# SensWear_MCU.net
KiCad netlist of a schematic drawn in Altium Designer
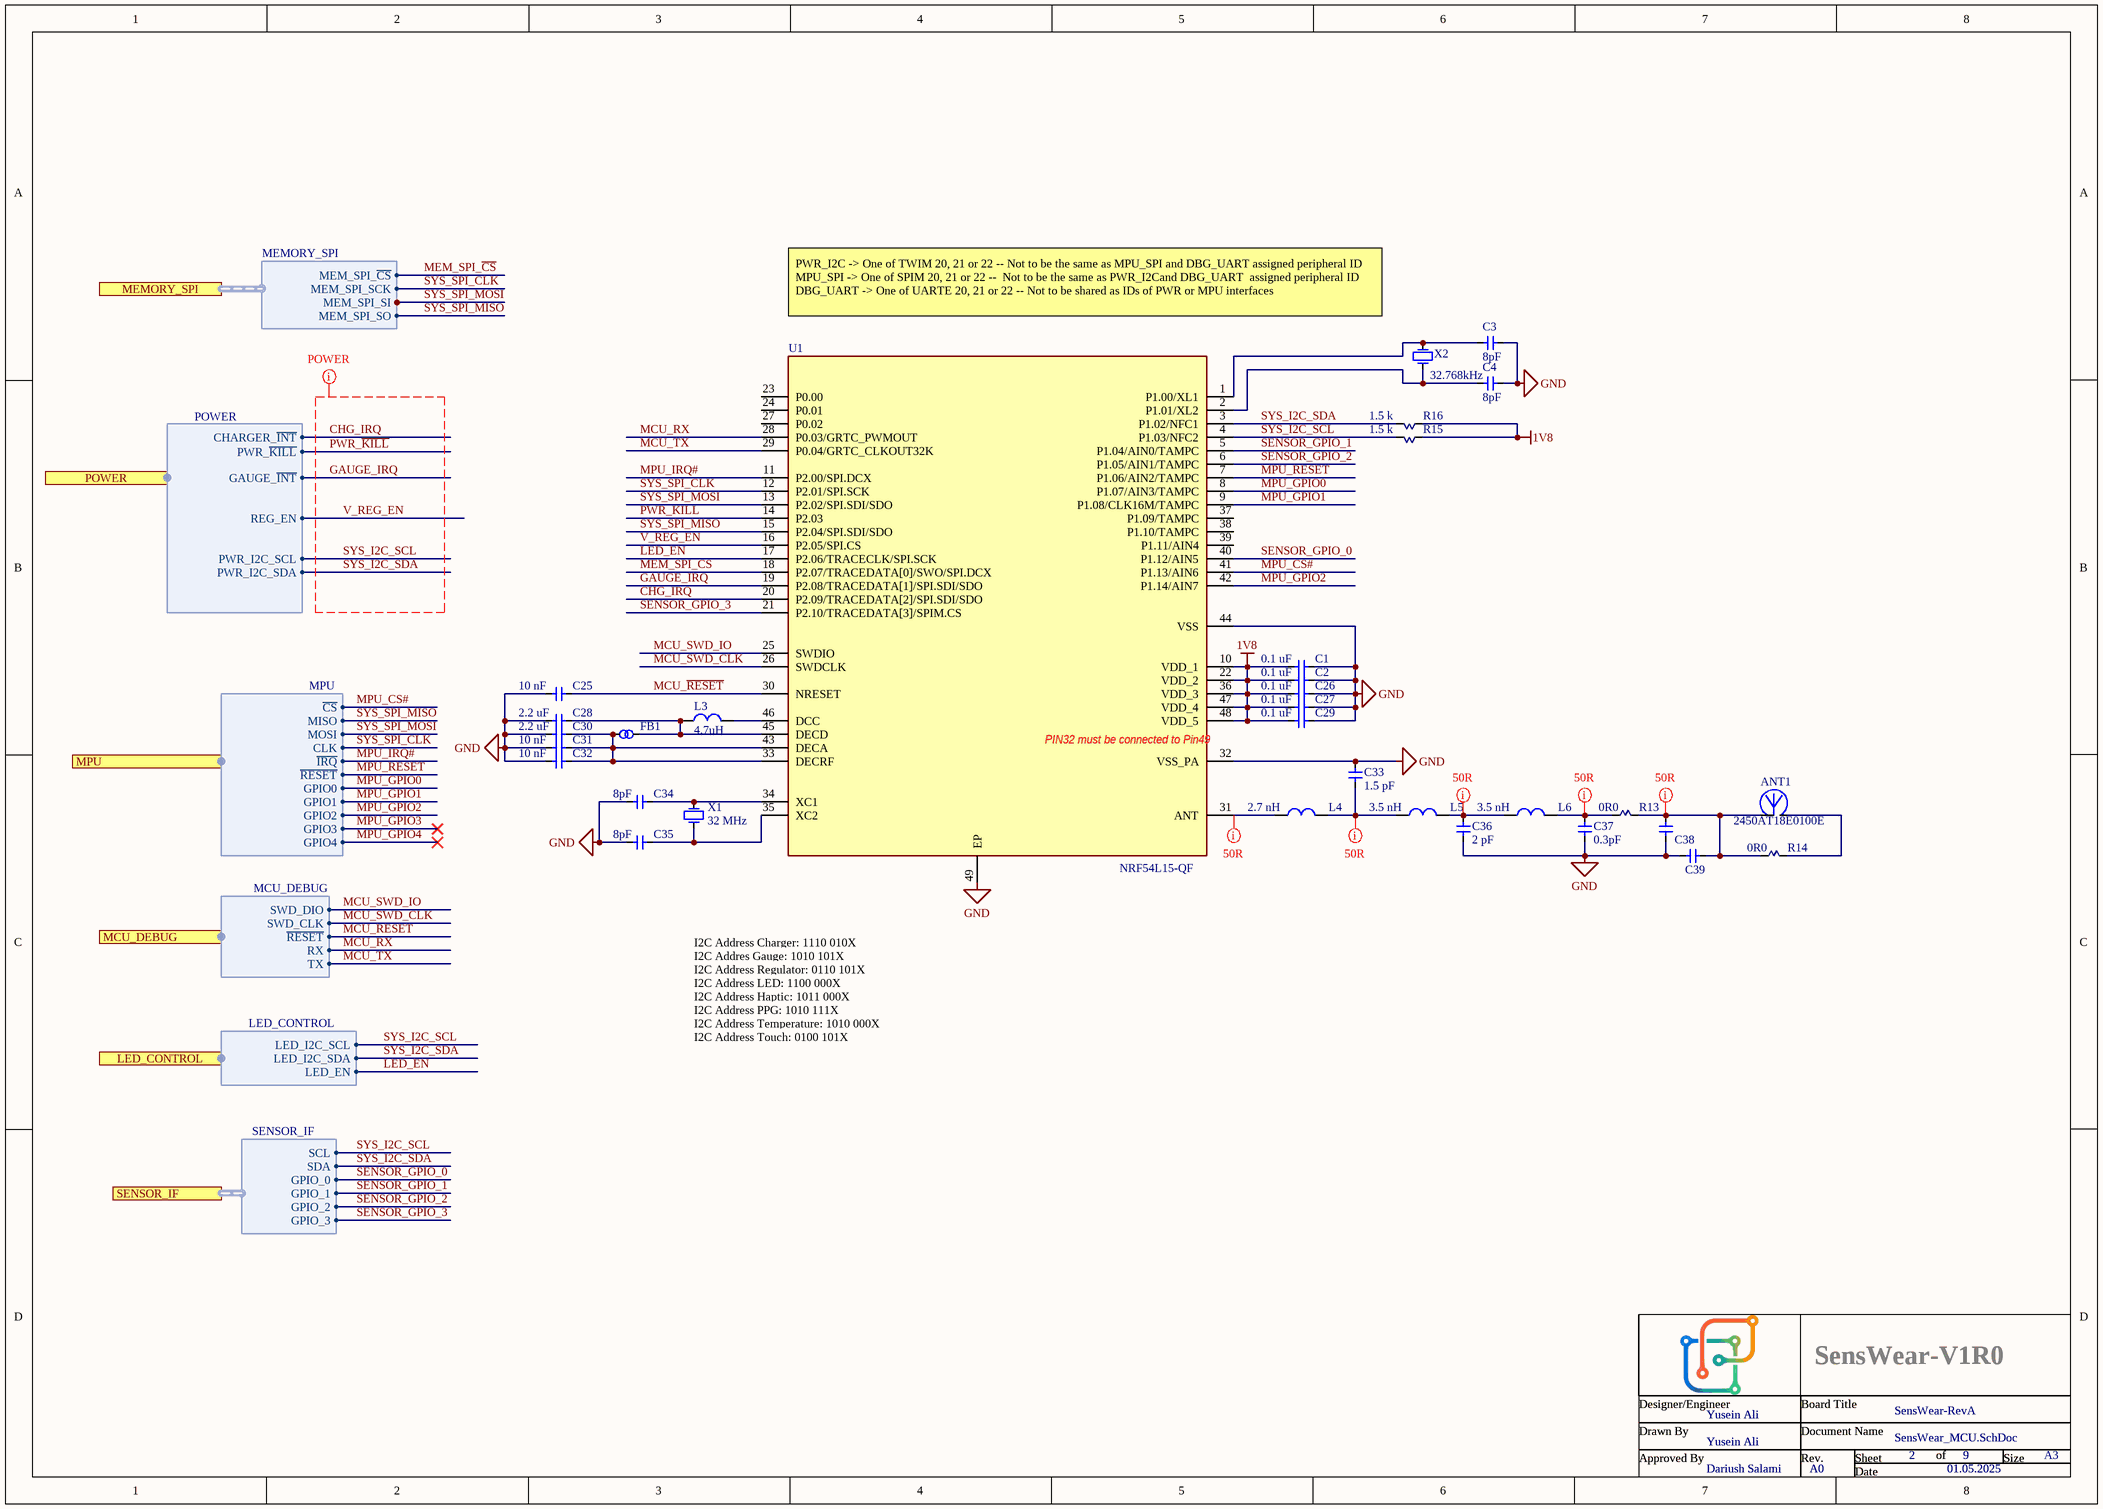
[diagram p0: SensWear_MCU.SchDoc]

(export (version "E")
  (design (tool "Eeschema 10.0.6"))
  (components
    (comp (ref "ANT1")
      (value "2450AT18E0100E")
      (footprint "ANTC3216X130N")
      (description "7 Inch Reel / Mini 2.45Ghz Chip Antenna")
      (fields (field (name "MANUFACTURER") "Johanson") (field (name "CHECKED") "TRUE"))
      (libsource (lib "RFComponents") (part "2450AT18E0100E"))
    )
    (comp (ref "C1")
      (value "0.1 uF")
      (footprint "CAPC1005X05N")
      (description "CAP CER 0.1UF 16V X5R 0402")
      (fields
        (field (name "MANUFACTURER") "Murata Electronics")
        (field (name "MANUFACTURER PART NUMBER") "GRM155R61C104KA88D")
      )
      (libsource (lib "OpenRingComponents") (part "GRM155R61C104KA88D"))
    )
    (comp (ref "C2")
      (value "0.1 uF")
      (footprint "CAPC1005X05N")
      (description "CAP CER 0.1UF 16V X5R 0402")
      (fields
        (field (name "MANUFACTURER") "Murata Electronics")
        (field (name "MANUFACTURER PART NUMBER") "GRM155R61C104KA88D")
      )
      (libsource (lib "OpenRingComponents") (part "GRM155R61C104KA88D"))
    )
    (comp (ref "C3")
      (value "8pF")
      (footprint "CAPC1005X05N")
      (description "Multilayer Ceramic Capacitors MLCC - SMD/SMT 0402 8.0pF 50volts C0G +/-0.05pF")
      (fields
        (field (name "MANUFACTURER") "Murata")
        (field (name "MANUFACTURER PART NUMBER") "GRM1555C1H8R0BA01D")
      )
      (libsource (lib "OpenRingComponents") (part "GRM1555C1H8R0BA01D"))
    )
    (comp (ref "C4")
      (value "8pF")
      (footprint "CAPC1005X05N")
      (description "Multilayer Ceramic Capacitors MLCC - SMD/SMT 0402 8.0pF 50volts C0G +/-0.05pF")
      (fields
        (field (name "MANUFACTURER") "Murata")
        (field (name "MANUFACTURER PART NUMBER") "GRM1555C1H8R0BA01D")
      )
      (libsource (lib "OpenRingComponents") (part "GRM1555C1H8R0BA01D"))
    )
    (comp (ref "C25")
      (value "10 nF")
      (footprint "CAPC1005X05N")
      (description "CAP CER 10000PF 50V X7R 0402")
      (fields
        (field (name "MANUFACTURER") "Murata Electronics North America")
        (field (name "MANUFACTURER PART NUMBER") "GRM155R71H103KA88D")
      )
      (libsource (lib "OpenRingComponents") (part "GRM155R71H103KA88D"))
    )
    (comp (ref "C26")
      (value "0.1 uF")
      (footprint "CAPC1005X05N")
      (description "CAP CER 0.1UF 16V X5R 0402")
      (fields
        (field (name "MANUFACTURER") "Murata Electronics")
        (field (name "MANUFACTURER PART NUMBER") "GRM155R61C104KA88D")
      )
      (libsource (lib "OpenRingComponents") (part "GRM155R61C104KA88D"))
    )
    (comp (ref "C27")
      (value "0.1 uF")
      (footprint "CAPC1005X05N")
      (description "CAP CER 0.1UF 16V X5R 0402")
      (fields
        (field (name "MANUFACTURER") "Murata Electronics")
        (field (name "MANUFACTURER PART NUMBER") "GRM155R61C104KA88D")
      )
      (libsource (lib "OpenRingComponents") (part "GRM155R61C104KA88D"))
    )
    (comp (ref "C28")
      (value "2.2 uF")
      (footprint "CAPC1005X05N")
      (description "CAP CER 2.2UF 10V X5R 0402")
      (fields
        (field (name "MANUFACTURER") "Murata Electronics North America")
        (field (name "MANUFACTURER PART NUMBER") "GRM155R61A225KE95D")
      )
      (libsource (lib "OpenRingComponents") (part "GRM155R61A225KE95D"))
    )
    (comp (ref "C29")
      (value "0.1 uF")
      (footprint "CAPC1005X05N")
      (description "CAP CER 0.1UF 16V X5R 0402")
      (fields
        (field (name "MANUFACTURER") "Murata Electronics")
        (field (name "MANUFACTURER PART NUMBER") "GRM155R61C104KA88D")
      )
      (libsource (lib "OpenRingComponents") (part "GRM155R61C104KA88D"))
    )
    (comp (ref "C30")
      (value "2.2 uF")
      (footprint "CAPC1005X05N")
      (description "CAP CER 2.2UF 10V X5R 0402")
      (fields
        (field (name "MANUFACTURER") "Murata Electronics North America")
        (field (name "MANUFACTURER PART NUMBER") "GRM155R61A225KE95D")
      )
      (libsource (lib "OpenRingComponents") (part "GRM155R61A225KE95D"))
    )
    (comp (ref "C31")
      (value "10 nF")
      (footprint "CAPC1005X05N")
      (description "CAP CER 10000PF 50V X7R 0402")
      (fields
        (field (name "MANUFACTURER") "Murata Electronics North America")
        (field (name "MANUFACTURER PART NUMBER") "GRM155R71H103KA88D")
      )
      (libsource (lib "OpenRingComponents") (part "GRM155R71H103KA88D"))
    )
    (comp (ref "C32")
      (value "10 nF")
      (footprint "CAPC1005X05N")
      (description "CAP CER 10000PF 50V X7R 0402")
      (fields
        (field (name "MANUFACTURER") "Murata Electronics North America")
        (field (name "MANUFACTURER PART NUMBER") "GRM155R71H103KA88D")
      )
      (libsource (lib "OpenRingComponents") (part "GRM155R71H103KA88D"))
    )
    (comp (ref "C33")
      (value "1.5 pF")
      (footprint "CAPC1005X05N")
      (description "Multilayer Ceramic Capacitor, 1.5 pF, 50 V, ï¿½ 0.1pF, C0G (NP0), 0402 [1005 Metric]")
      (fields
        (field (name "MANUFACTURER") "Murata")
        (field (name "MANUFACTURER PART NUMBER") "GJM1555C1H1R5BB01D")
      )
      (libsource (lib "OpenRingComponents") (part "GJM1555C1H1R5BB01D"))
    )
    (comp (ref "C34")
      (value "8pF")
      (footprint "CAPC1005X05N")
      (description "Multilayer Ceramic Capacitors MLCC - SMD/SMT 0402 8.0pF 50volts C0G +/-0.05pF")
      (fields
        (field (name "MANUFACTURER") "Murata")
        (field (name "MANUFACTURER PART NUMBER") "GRM1555C1H8R0BA01D")
      )
      (libsource (lib "OpenRingComponents") (part "GRM1555C1H8R0BA01D"))
    )
    (comp (ref "C35")
      (value "8pF")
      (footprint "CAPC1005X05N")
      (description "Multilayer Ceramic Capacitors MLCC - SMD/SMT 0402 8.0pF 50volts C0G +/-0.05pF")
      (fields
        (field (name "MANUFACTURER") "Murata")
        (field (name "MANUFACTURER PART NUMBER") "GRM1555C1H8R0BA01D")
      )
      (libsource (lib "OpenRingComponents") (part "GRM1555C1H8R0BA01D"))
    )
    (comp (ref "C36")
      (value "2 pF")
      (footprint "CAPC1005X05N")
      (description "0402 2 pF 50V ±0.05 pF Tolerance C0G SMT Multilayer Ceramic Capacitor")
      (fields
        (field (name "MANUFACTURER") "Murata")
        (field (name "MANUFACTURER PART NUMBER") "GJM1555C1H2R0WB01D")
      )
      (libsource (lib "Passives") (part "GJM1555C1H2R0WB01D"))
    )
    (comp (ref "C37")
      (value "0.3pF")
      (footprint "INDC1005X06N")
      (description "0402 0.3 pF 50V ±0.05 pF Tolerance C0G SMT Multilayer Ceramic Capacitor")
      (fields
        (field (name "MANUFACTURER") "Murata")
        (field (name "MANUFACTURER PART NUMBER") "GJM1555C1HR30WB01D")
      )
      (libsource (lib "OpenRingComponents") (part "GJM1555C1HR30WB01D"))
    )
    (comp (ref "C38")
      (value "NC")
      (footprint "CAPC1005X05N")
      (libsource (lib "OpenRingComponents") (part "CAPACITOR"))
    )
    (comp (ref "C39")
      (value "NC")
      (footprint "CAPC1005X05N")
      (libsource (lib "OpenRingComponents") (part "CAPACITOR"))
    )
    (comp (ref "FB1")
      (value "BLM15AG121SN1D")
      (footprint "INDC1005X06N")
      (description "Ferrite Beads Multi-Layer 120Ohm 25% 100MHz 550mA 190mOhm DCR 0402 Paper T/R")
      (fields (field (name "MANUFACTURER") "Murata") (field (name "TOLERANCE") "25%"))
      (libsource (lib "OpenRingComponents") (part "BLM15AG121SN1D"))
    )
    (comp (ref "L3")
      (value "4.7uH")
      (footprint "INDC1005X06N")
      (description "Inductor Power Chip Shielded Multi-Layer 4.7uH 20% 1MHz Ferrite 0.08A 0.78Ohm DCR 0603 T/R")
      (fields
        (field (name "MANUFACTURER") "Murata")
        (field (name "MANUFACTURER PART NUMBER") "LQM18FN4R7M00D")
      )
      (libsource (lib "Passives") (part "LQM18FN4R7M00D"))
    )
    (comp (ref "L4")
      (value "2.7 nH")
      (footprint "INDC1005X06N")
      (description "Inductor Chip 2.7nH 0.1nH Tolerance 2-Pin 0402 Paper T/R")
      (fields
        (field (name "MANUFACTURER") "Murata")
        (field (name "MANUFACTURER PART NUMBER") "LQG15WH2N7B02D")
      )
      (libsource (lib "OpenRingComponents") (part "LQG15WH2N7B02D"))
    )
    (comp (ref "L5")
      (value "3.5 nH")
      (footprint "INDC1005X06N")
      (description "Inductor Chip 3.5nH 0.1nH Tolerance 2-Pin 0402 Paper T/R")
      (fields
        (field (name "MANUFACTURER") "Murata")
        (field (name "MANUFACTURER PART NUMBER") "LQG15WH3N5B02D")
      )
      (libsource (lib "OpenRingComponents") (part "LQG15WH3N5B02D"))
    )
    (comp (ref "L6")
      (value "3.5 nH")
      (footprint "INDC1005X06N")
      (description "Inductor Chip 3.5nH 0.1nH Tolerance 2-Pin 0402 Paper T/R")
      (fields
        (field (name "MANUFACTURER") "Murata")
        (field (name "MANUFACTURER PART NUMBER") "LQG15WH3N5B02D")
      )
      (libsource (lib "OpenRingComponents") (part "LQG15WH3N5B02D"))
    )
    (comp (ref "R13")
      (value "0R0")
      (footprint "RESC1005X04N")
      (description "RES SMD 0.0OHM JUMPER 1/10W 0402")
      (fields
        (field (name "MANUFACTURER") "Panasonic Electronic Components")
        (field (name "MANUFACTURER PART NUMBER") "ERJ-2GE0R00X")
      )
      (libsource (lib "OpenRingComponents") (part "ERJ-2GE0R00X"))
    )
    (comp (ref "R14")
      (value "0R0")
      (footprint "RESC1005X04N")
      (description "RES SMD 0.0OHM JUMPER 1/10W 0402")
      (fields
        (field (name "MANUFACTURER") "Panasonic Electronic Components")
        (field (name "MANUFACTURER PART NUMBER") "ERJ-2GE0R00X")
      )
      (libsource (lib "OpenRingComponents") (part "ERJ-2GE0R00X"))
    )
    (comp (ref "R15")
      (value "1.5 k")
      (footprint "RESC1005X04N")
      (description "RES SMD 1.5K OHM 1% 1/10W 0402")
      (fields
        (field (name "MANUFACTURER") "Panasonic Electronic Components")
        (field (name "MANUFACTURER PART NUMBER") "ERJ-2RKF1501X")
      )
      (libsource (lib "OpenRingComponents") (part "ERJ-2RKF1501X"))
    )
    (comp (ref "R16")
      (value "1.5 k")
      (footprint "RESC1005X04N")
      (description "RES SMD 1.5K OHM 1% 1/10W 0402")
      (fields
        (field (name "MANUFACTURER") "Panasonic Electronic Components")
        (field (name "MANUFACTURER PART NUMBER") "ERJ-2RKF1501X")
      )
      (libsource (lib "OpenRingComponents") (part "ERJ-2RKF1501X"))
    )
    (comp (ref "U1")
      (value "NRF54L15-QF")
      (footprint "QFN40P600X600X95-49N")
      (description "nRF54L15 SoC with Arm Cortex-M33 processor")
      (fields
        (field (name "MANUFACTURER") "Nordic Semiconductor")
        (field (name "MANUFACTURER PART NUMBER") "NRF54L15-QFAA-R")
      )
      (libsource (lib "OpenRingComponents") (part "NRF54L15-QFAA-R"))
    )
    (comp (ref "X1")
      (value "32 MHz")
      (footprint "FP-ABM11W-MFG")
      (description "CRYSTAL 32.0000MHZ 8PF SMD, 2x1.6mm, RoHS")
      (fields
        (field (name "MANUFACTURER") "Abracon")
        (field (name "MANUFACTURER PART NUMBER") "ABM11W-32.0000MHZ-8-B1U-T3")
        (field (name "CHECKED") "TRUE")
      )
      (libsource (lib "Passives") (part "ABM11W-32.0000MHZ-8-B1U-T3"))
    )
    (comp (ref "X2")
      (value "32.768kHz")
      (footprint "Abracon_ABS6_2012X06L")
      (description "CRYSTAL 32.768 KHZ 12.5 PF SMD")
      (fields
        (field (name "MANUFACTURER") "Abracon Corporation")
        (field (name "MANUFACTURER PART NUMBER") "ABS06-32.768KHZ-1-T")
      )
      (libsource (lib "OpenRingComponents") (part "ABS06-32.768KHZ-1-T"))
    )
  )
  (nets
    (net (code "7") (name "/CHG_IRQ") (class "Default")
      (node (ref "U1") (pin "20") (pinfunction "P2.09/TRACEDATA[2]/SPI.SDI/SDO_20") (pintype "passive"))
    )
    (net (code "8") (name "/GAUGE_IRQ") (class "Default")
      (node (ref "U1") (pin "19") (pinfunction "P2.08/TRACEDATA[1]/SPI.SDI/SDO_19") (pintype "passive"))
    )
    (net (code "9") (name "/LED_EN") (class "Default")
      (node (ref "U1") (pin "17") (pinfunction "P2.06/TRACECLK/SPI.SCK_17") (pintype "passive"))
    )
    (net (code "10") (name "/MCU_RX") (class "Default")
      (node (ref "U1") (pin "28") (pinfunction "P0.03/GRTC_PWMOUT_28") (pintype "passive"))
    )
    (net (code "11") (name "/MCU_SWD_CLK") (class "Default")
      (node (ref "U1") (pin "26") (pinfunction "SWDCLK_26") (pintype "passive"))
    )
    (net (code "12") (name "/MCU_SWD_IO") (class "Default")
      (node (ref "U1") (pin "25") (pinfunction "SWDIO_25") (pintype "passive"))
    )
    (net (code "13") (name "/MCU_TX") (class "Default")
      (node (ref "U1") (pin "29") (pinfunction "P0.04/GRTC_CLKOUT32K_29") (pintype "passive"))
    )
    (net (code "14") (name "/MCU_~{RESET}") (class "Default")
      (node (ref "C25") (pin "2") (pinfunction "2_2") (pintype "passive"))
      (node (ref "U1") (pin "30") (pinfunction "NRESET_30") (pintype "passive"))
    )
    (net (code "15") (name "/MEM_SPI_~{CS}") (class "Default")
      (node (ref "U1") (pin "18") (pinfunction "P2.07/TRACEDATA[0]/SWO/SPI.DCX_18") (pintype "passive"))
    )
    (net (code "16") (name "/MPU_CS#") (class "Default")
      (node (ref "U1") (pin "41") (pinfunction "P1.13/AIN6_41") (pintype "passive"))
    )
    (net (code "17") (name "/MPU_GPIO0") (class "Default")
      (node (ref "U1") (pin "8") (pinfunction "P1.07/AIN3/TAMPC_8") (pintype "passive"))
    )
    (net (code "18") (name "/MPU_GPIO1") (class "Default")
      (node (ref "U1") (pin "9") (pinfunction "P1.08/CLK16M/TAMPC_9") (pintype "passive"))
    )
    (net (code "19") (name "/MPU_GPIO2") (class "Default")
      (node (ref "U1") (pin "42") (pinfunction "P1.14/AIN7_42") (pintype "passive"))
    )
    (net (code "22") (name "/MPU_IRQ#") (class "Default")
      (node (ref "U1") (pin "11") (pinfunction "P2.00/SPI.DCX_11") (pintype "passive"))
    )
    (net (code "23") (name "/MPU_~{RESET}") (class "Default")
      (node (ref "U1") (pin "7") (pinfunction "P1.06/AIN2/TAMPC_7") (pintype "passive"))
    )
    (net (code "24") (name "/PWR_~{KILL}") (class "Default")
      (node (ref "U1") (pin "14") (pinfunction "P2.03_14") (pintype "passive"))
    )
    (net (code "25") (name "/SENSOR_GPIO_0") (class "Default")
      (node (ref "U1") (pin "40") (pinfunction "P1.12/AIN5_40") (pintype "passive"))
    )
    (net (code "26") (name "/SENSOR_GPIO_1") (class "Default")
      (node (ref "U1") (pin "5") (pinfunction "P1.04/AIN0/TAMPC_5") (pintype "passive"))
    )
    (net (code "27") (name "/SENSOR_GPIO_2") (class "Default")
      (node (ref "U1") (pin "6") (pinfunction "P1.05/AIN1/TAMPC_6") (pintype "passive"))
    )
    (net (code "28") (name "/SENSOR_GPIO_3") (class "Default")
      (node (ref "U1") (pin "21") (pinfunction "P2.10/TRACEDATA[3]/SPIM.CS_21") (pintype "passive"))
    )
    (net (code "29") (name "/SYS_I2C_SCL") (class "Default")
      (node (ref "R15") (pin "2") (pinfunction "2_2") (pintype "passive"))
      (node (ref "U1") (pin "4") (pinfunction "P1.03/NFC2_4") (pintype "passive"))
    )
    (net (code "30") (name "/SYS_I2C_SDA") (class "Default")
      (node (ref "R16") (pin "2") (pinfunction "2_2") (pintype "passive"))
      (node (ref "U1") (pin "3") (pinfunction "P1.02/NFC1_3") (pintype "passive"))
    )
    (net (code "31") (name "/SYS_SPI_CLK") (class "Default")
      (node (ref "U1") (pin "12") (pinfunction "P2.01/SPI.SCK_12") (pintype "passive"))
    )
    (net (code "32") (name "/SYS_SPI_MISO") (class "Default")
      (node (ref "U1") (pin "15") (pinfunction "P2.04/SPI.SDI/SDO_15") (pintype "passive"))
    )
    (net (code "33") (name "/SYS_SPI_MOSI") (class "Default")
      (node (ref "U1") (pin "13") (pinfunction "P2.02/SPI.SDI/SDO_13") (pintype "passive"))
    )
    (net (code "34") (name "/V_REG_EN") (class "Default")
      (node (ref "U1") (pin "16") (pinfunction "P2.05/SPI.CS_16") (pintype "passive"))
    )
    (net (code "41") (name "1V8") (class "Default")
      (node (ref "C1") (pin "1") (pinfunction "1_1") (pintype "passive"))
      (node (ref "C2") (pin "1") (pinfunction "1_1") (pintype "passive"))
      (node (ref "C26") (pin "1") (pinfunction "1_1") (pintype "passive"))
      (node (ref "C27") (pin "1") (pinfunction "1_1") (pintype "passive"))
      (node (ref "C29") (pin "1") (pinfunction "1_1") (pintype "passive"))
      (node (ref "R15") (pin "1") (pinfunction "1_1") (pintype "passive"))
      (node (ref "R16") (pin "1") (pinfunction "1_1") (pintype "passive"))
      (node (ref "U1") (pin "10") (pinfunction "VDD_1_10") (pintype "passive"))
      (node (ref "U1") (pin "22") (pinfunction "VDD_2_22") (pintype "passive"))
      (node (ref "U1") (pin "36") (pinfunction "VDD_3_36") (pintype "passive"))
      (node (ref "U1") (pin "47") (pinfunction "VDD_4_47") (pintype "passive"))
      (node (ref "U1") (pin "48") (pinfunction "VDD_5_48") (pintype "passive"))
    )
    (net (code "42") (name "GND") (class "Default")
      (node (ref "C1") (pin "2") (pinfunction "2_2") (pintype "passive"))
      (node (ref "C2") (pin "2") (pinfunction "2_2") (pintype "passive"))
      (node (ref "C25") (pin "1") (pinfunction "1_1") (pintype "passive"))
      (node (ref "C26") (pin "2") (pinfunction "2_2") (pintype "passive"))
      (node (ref "C27") (pin "2") (pinfunction "2_2") (pintype "passive"))
      (node (ref "C28") (pin "1") (pinfunction "1_1") (pintype "passive"))
      (node (ref "C29") (pin "2") (pinfunction "2_2") (pintype "passive"))
      (node (ref "C3") (pin "2") (pinfunction "2_2") (pintype "passive"))
      (node (ref "C30") (pin "1") (pinfunction "1_1") (pintype "passive"))
      (node (ref "C31") (pin "1") (pinfunction "1_1") (pintype "passive"))
      (node (ref "C32") (pin "1") (pinfunction "1_1") (pintype "passive"))
      (node (ref "C33") (pin "2") (pinfunction "2_2") (pintype "passive"))
      (node (ref "C34") (pin "1") (pinfunction "1_1") (pintype "passive"))
      (node (ref "C35") (pin "1") (pinfunction "1_1") (pintype "passive"))
      (node (ref "C36") (pin "1") (pinfunction "1_1") (pintype "passive"))
      (node (ref "C37") (pin "1") (pinfunction "1_1") (pintype "passive"))
      (node (ref "C38") (pin "1") (pinfunction "1_1") (pintype "passive"))
      (node (ref "C39") (pin "2") (pinfunction "2_2") (pintype "passive"))
      (node (ref "C4") (pin "1") (pinfunction "1_1") (pintype "passive"))
      (node (ref "U1") (pin "32") (pinfunction "VSS_PA_32") (pintype "passive"))
      (node (ref "U1") (pin "44") (pinfunction "VSS_44") (pintype "passive"))
      (node (ref "U1") (pin "49") (pinfunction "EP_49") (pintype "passive"))
    )
    (net (code "43") (name "Net-(ANT1-Pad1)") (class "Default")
      (node (ref "ANT1") (pin "1") (pinfunction "1_1") (pintype "passive"))
      (node (ref "C38") (pin "2") (pinfunction "2_2") (pintype "passive"))
      (node (ref "C39") (pin "1") (pinfunction "1_1") (pintype "passive"))
      (node (ref "R13") (pin "2") (pinfunction "2_2") (pintype "passive"))
      (node (ref "R14") (pin "1") (pinfunction "1_1") (pintype "passive"))
    )
    (net (code "44") (name "Net-(ANT1-Pad2)") (class "Default")
      (node (ref "ANT1") (pin "2") (pinfunction "2_2") (pintype "passive"))
      (node (ref "R14") (pin "2") (pinfunction "2_2") (pintype "passive"))
    )
    (net (code "45") (name "Net-(C33-Pad1)") (class "Default")
      (node (ref "C33") (pin "1") (pinfunction "1_1") (pintype "passive"))
      (node (ref "L4") (pin "2") (pinfunction "2_2") (pintype "passive"))
      (node (ref "L5") (pin "1") (pinfunction "1_1") (pintype "passive"))
    )
    (net (code "46") (name "Net-(C36-Pad2)") (class "Default")
      (node (ref "C36") (pin "2") (pinfunction "2_2") (pintype "passive"))
      (node (ref "L5") (pin "2") (pinfunction "2_2") (pintype "passive"))
      (node (ref "L6") (pin "1") (pinfunction "1_1") (pintype "passive"))
    )
    (net (code "47") (name "Net-(C37-Pad2)") (class "Default")
      (node (ref "C37") (pin "2") (pinfunction "2_2") (pintype "passive"))
      (node (ref "L6") (pin "2") (pinfunction "2_2") (pintype "passive"))
      (node (ref "R13") (pin "1") (pinfunction "1_1") (pintype "passive"))
    )
    (net (code "48") (name "Net-(U1-ANT)") (class "Default")
      (node (ref "L4") (pin "1") (pinfunction "1_1") (pintype "passive"))
      (node (ref "U1") (pin "31") (pinfunction "ANT_31") (pintype "passive"))
    )
    (net (code "49") (name "Net-(U1-DCC)") (class "Default")
      (node (ref "L3") (pin "2") (pinfunction "2_2") (pintype "passive"))
      (node (ref "U1") (pin "46") (pinfunction "DCC_46") (pintype "passive"))
    )
    (net (code "50") (name "Net-(U1-DECA)") (class "Default")
      (node (ref "C30") (pin "2") (pinfunction "2_2") (pintype "passive"))
      (node (ref "C31") (pin "2") (pinfunction "2_2") (pintype "passive"))
      (node (ref "C32") (pin "2") (pinfunction "2_2") (pintype "passive"))
      (node (ref "FB1") (pin "1") (pinfunction "1_1") (pintype "passive"))
      (node (ref "U1") (pin "33") (pinfunction "DECRF_33") (pintype "passive"))
      (node (ref "U1") (pin "43") (pinfunction "DECA_43") (pintype "passive"))
    )
    (net (code "51") (name "Net-(U1-DECD)") (class "Default")
      (node (ref "C28") (pin "2") (pinfunction "2_2") (pintype "passive"))
      (node (ref "FB1") (pin "2") (pinfunction "2_2") (pintype "passive"))
      (node (ref "L3") (pin "1") (pinfunction "1_1") (pintype "passive"))
      (node (ref "U1") (pin "45") (pinfunction "DECD_45") (pintype "passive"))
    )
    (net (code "52") (name "Net-(U1-P1.00{slash}XL1)") (class "Default")
      (node (ref "C3") (pin "1") (pinfunction "1_1") (pintype "passive"))
      (node (ref "U1") (pin "1") (pinfunction "P1.00/XL1_1") (pintype "passive"))
      (node (ref "X2") (pin "2") (pinfunction "OSC2_2") (pintype "passive"))
    )
    (net (code "53") (name "Net-(U1-P1.01{slash}XL2)") (class "Default")
      (node (ref "C4") (pin "2") (pinfunction "2_2") (pintype "passive"))
      (node (ref "U1") (pin "2") (pinfunction "P1.01/XL2_2") (pintype "passive"))
      (node (ref "X2") (pin "1") (pinfunction "OSC1_1") (pintype "passive"))
    )
    (net (code "54") (name "Net-(U1-XC1)") (class "Default")
      (node (ref "C34") (pin "2") (pinfunction "2_2") (pintype "passive"))
      (node (ref "U1") (pin "34") (pinfunction "XC1_34") (pintype "passive"))
      (node (ref "X1") (pin "3") (pinfunction "OSC2_3") (pintype "passive"))
    )
    (net (code "55") (name "Net-(U1-XC2)") (class "Default")
      (node (ref "C35") (pin "2") (pinfunction "2_2") (pintype "passive"))
      (node (ref "U1") (pin "35") (pinfunction "XC2_35") (pintype "passive"))
      (node (ref "X1") (pin "1") (pinfunction "OSC1_1") (pintype "passive"))
    )
    (net (code "56") (name "unconnected-(U1-P0.00-Pad23)") (class "Default")
      (node (ref "U1") (pin "23") (pinfunction "P0.00_23") (pintype "passive"))
    )
    (net (code "57") (name "unconnected-(U1-P0.01-Pad24)") (class "Default")
      (node (ref "U1") (pin "24") (pinfunction "P0.01_24") (pintype "passive"))
    )
    (net (code "58") (name "unconnected-(U1-P0.02-Pad27)") (class "Default")
      (node (ref "U1") (pin "27") (pinfunction "P0.02_27") (pintype "passive"))
    )
    (net (code "59") (name "unconnected-(U1-P1.09{slash}TAMPC-Pad37)") (class "Default")
      (node (ref "U1") (pin "37") (pinfunction "P1.09/TAMPC_37") (pintype "passive"))
    )
    (net (code "60") (name "unconnected-(U1-P1.10{slash}TAMPC-Pad38)") (class "Default")
      (node (ref "U1") (pin "38") (pinfunction "P1.10/TAMPC_38") (pintype "passive"))
    )
    (net (code "61") (name "unconnected-(U1-P1.11{slash}AIN4-Pad39)") (class "Default")
      (node (ref "U1") (pin "39") (pinfunction "P1.11/AIN4_39") (pintype "passive"))
    )
  )
)
